# Main.net
KiCad netlist of a schematic drawn in Altium Designer
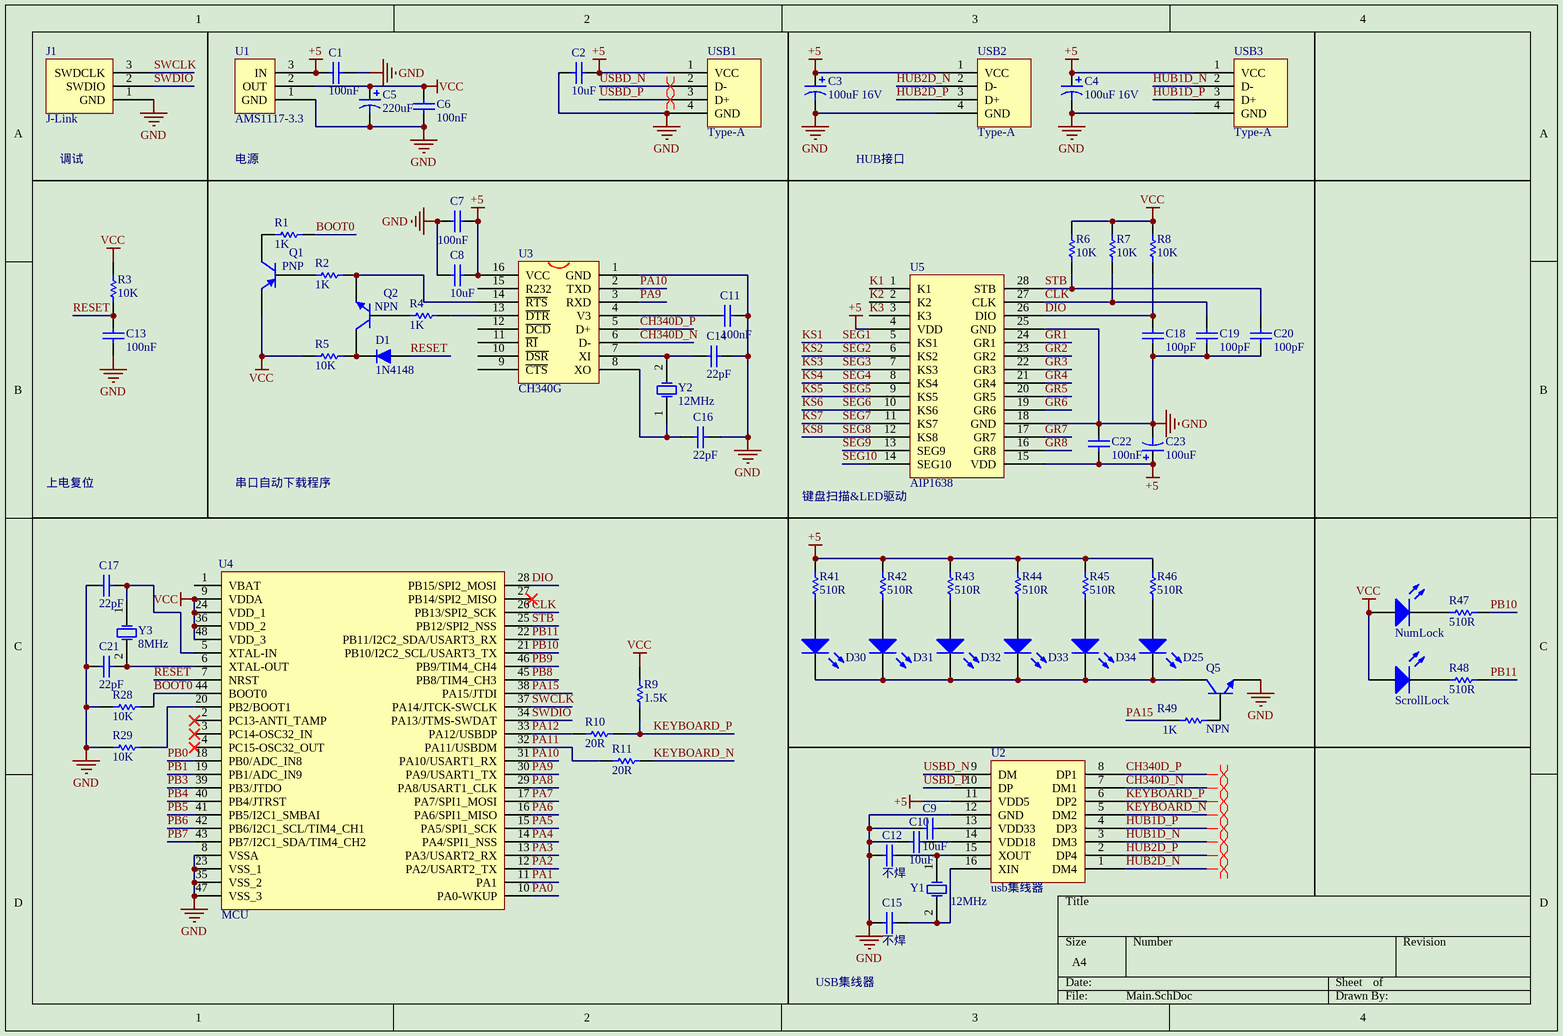
[diagram p0: Main.SchDoc]

(export (version "E")
  (design (tool "Eeschema 10.0.6"))
  (components
    (comp (ref "C1")
      (value "100nF")
      (footprint "LC-1206_C")
      (description "Capacitor")
      (fields (field (name "PUBLISHER") "Altium Limited"))
      (libsource (lib "键盘") (part "Capacitor"))
    )
    (comp (ref "C2")
      (value "10uF")
      (footprint "LC-0603_C")
      (description "Capacitor")
      (fields (field (name "PUBLISHER") "Altium Limited"))
      (libsource (lib "键盘") (part "Capacitor"))
    )
    (comp (ref "C3")
      (value "100uF 16V")
      (footprint "贴片电解 6.3*5.4")
      (description "Polarized Capacitor (Axial)")
      (fields (field (name "PUBLISHER") "Altium Limited"))
      (libsource (lib "键盘") (part "Cap Pol"))
    )
    (comp (ref "C4")
      (value "100uF 16V")
      (footprint "贴片电解 6.3*5.4")
      (description "Polarized Capacitor (Axial)")
      (fields (field (name "PUBLISHER") "Altium Limited"))
      (libsource (lib "键盘") (part "Cap Pol"))
    )
    (comp (ref "C5")
      (value "220uF")
      (footprint "自用库:贴片电解 8*10.2")
      (description "Polarized Capacitor (Axial)")
      (fields (field (name "PUBLISHER") "Altium Limited"))
      (libsource (lib "键盘") (part "Cap Pol"))
    )
    (comp (ref "C6")
      (value "100nF")
      (footprint "LC-1206_C")
      (description "Capacitor")
      (fields (field (name "PUBLISHER") "Altium Limited"))
      (libsource (lib "键盘") (part "Capacitor"))
    )
    (comp (ref "C7")
      (value "100nF")
      (footprint "LC-1206_C")
      (description "Capacitor")
      (fields (field (name "PUBLISHER") "Altium Limited"))
      (libsource (lib "键盘") (part "Capacitor"))
    )
    (comp (ref "C8")
      (value "10uF")
      (footprint "LC-0603_C")
      (description "Capacitor")
      (fields (field (name "PUBLISHER") "Altium Limited"))
      (libsource (lib "键盘") (part "Capacitor"))
    )
    (comp (ref "C9")
      (value "10uF")
      (footprint "LC-0603_C")
      (description "Capacitor")
      (fields (field (name "PUBLISHER") "Altium Limited"))
      (libsource (lib "键盘") (part "Capacitor"))
    )
    (comp (ref "C10")
      (value "10uF")
      (footprint "LC-0603_C")
      (description "Capacitor")
      (fields (field (name "PUBLISHER") "Altium Limited"))
      (libsource (lib "键盘") (part "Capacitor"))
    )
    (comp (ref "C11")
      (value "100nF")
      (footprint "LC-1206_C")
      (description "Capacitor")
      (fields (field (name "PUBLISHER") "Altium Limited"))
      (libsource (lib "键盘") (part "Capacitor"))
    )
    (comp (ref "C12")
      (value "不焊")
      (footprint "LC-0603_C")
      (description "Capacitor")
      (fields (field (name "PUBLISHER") "Altium Limited"))
      (libsource (lib "键盘") (part "Capacitor"))
    )
    (comp (ref "C13")
      (value "100nF")
      (footprint "LC-1206_C")
      (description "Capacitor")
      (fields (field (name "PUBLISHER") "Altium Limited"))
      (libsource (lib "Keyboard") (part "Capacitor"))
    )
    (comp (ref "C14")
      (value "22pF")
      (footprint "LC-1206_C")
      (description "Capacitor")
      (fields (field (name "PUBLISHER") "Altium Limited"))
      (libsource (lib "键盘") (part "Capacitor"))
    )
    (comp (ref "C15")
      (value "不焊")
      (footprint "LC-0603_C")
      (description "Capacitor")
      (fields (field (name "PUBLISHER") "Altium Limited"))
      (libsource (lib "键盘") (part "Capacitor"))
    )
    (comp (ref "C16")
      (value "22pF")
      (footprint "LC-1206_C")
      (description "Capacitor")
      (fields (field (name "PUBLISHER") "Altium Limited"))
      (libsource (lib "键盘") (part "Capacitor"))
    )
    (comp (ref "C17")
      (value "22pF")
      (footprint "LC-1206_C")
      (description "Capacitor")
      (fields (field (name "PUBLISHER") "Altium Limited"))
      (libsource (lib "键盘") (part "Capacitor"))
    )
    (comp (ref "C18")
      (value "100pF")
      (footprint "LC-0603_C")
      (description "Capacitor")
      (fields (field (name "PUBLISHER") "Altium Limited"))
      (libsource (lib "键盘") (part "Capacitor"))
    )
    (comp (ref "C19")
      (value "100pF")
      (footprint "LC-0603_C")
      (description "Capacitor")
      (fields (field (name "PUBLISHER") "Altium Limited"))
      (libsource (lib "键盘") (part "Capacitor"))
    )
    (comp (ref "C20")
      (value "100pF")
      (footprint "LC-0603_C")
      (description "Capacitor")
      (fields (field (name "PUBLISHER") "Altium Limited"))
      (libsource (lib "键盘") (part "Capacitor"))
    )
    (comp (ref "C21")
      (value "22pF")
      (footprint "LC-1206_C")
      (description "Capacitor")
      (fields (field (name "PUBLISHER") "Altium Limited"))
      (libsource (lib "键盘") (part "Capacitor"))
    )
    (comp (ref "C22")
      (value "100nF")
      (footprint "LC-1206_C")
      (description "Capacitor")
      (fields (field (name "PUBLISHER") "Altium Limited"))
      (libsource (lib "键盘") (part "Capacitor"))
    )
    (comp (ref "C23")
      (value "100uF")
      (footprint "贴片电解 6.3*5.4")
      (description "Polarized Capacitor (Axial)")
      (fields (field (name "PUBLISHER") "Altium Limited"))
      (libsource (lib "键盘") (part "Cap Pol"))
    )
    (comp (ref "D1") (value "1N4148") (footprint "LC-DO-35") (libsource (lib "自用库") (part "DO-214AC 肖特基")))
    (comp (ref "D25")
      (value "LED")
      (footprint "LC-0603_LED_S3")
      (description "Typical INFRARED GaAs LED")
      (fields (field (name "PUBLISHER") "Altium Limited"))
      (libsource (lib "键盘") (part "LED"))
    )
    (comp (ref "D30")
      (value "LED")
      (footprint "LC-0603_LED_S3")
      (description "Typical INFRARED GaAs LED")
      (fields (field (name "PUBLISHER") "Altium Limited"))
      (libsource (lib "键盘") (part "LED"))
    )
    (comp (ref "D31")
      (value "LED")
      (footprint "LC-0603_LED_S3")
      (description "Typical INFRARED GaAs LED")
      (fields (field (name "PUBLISHER") "Altium Limited"))
      (libsource (lib "键盘") (part "LED"))
    )
    (comp (ref "D32")
      (value "LED")
      (footprint "LC-0603_LED_S3")
      (description "Typical INFRARED GaAs LED")
      (fields (field (name "PUBLISHER") "Altium Limited"))
      (libsource (lib "键盘") (part "LED"))
    )
    (comp (ref "D33")
      (value "LED")
      (footprint "LC-0603_LED_S3")
      (description "Typical INFRARED GaAs LED")
      (fields (field (name "PUBLISHER") "Altium Limited"))
      (libsource (lib "键盘") (part "LED"))
    )
    (comp (ref "D34")
      (value "LED")
      (footprint "LC-0603_LED_S3")
      (description "Typical INFRARED GaAs LED")
      (fields (field (name "PUBLISHER") "Altium Limited"))
      (libsource (lib "键盘") (part "LED"))
    )
    (comp (ref "J1") (value "J-Link") (footprint "IDE3") (libsource (lib "键盘") (part "J-Link")))
    (comp (ref "NumLock")
      (value "LED")
      (footprint "LC-0603_LED_S3")
      (description "Typical INFRARED GaAs LED")
      (fields (field (name "PUBLISHER") "Altium Limited"))
      (libsource (lib "键盘") (part "LED"))
    )
    (comp (ref "Q1")
      (value "PNP")
      (footprint "LC-SOT-23(SOT-23-3)")
      (description "PNP Bipolar Transistor")
      (fields (field (name "PUBLISHER") "Altium Limited"))
      (libsource (lib "键盘") (part "PNP"))
    )
    (comp (ref "Q2")
      (value "NPN")
      (footprint "LC-SOT-23(SOT-23-3)")
      (description "NPN Bipolar Transistor")
      (fields (field (name "PUBLISHER") "Altium Limited"))
      (libsource (lib "键盘") (part "NPN"))
    )
    (comp (ref "Q5")
      (value "NPN")
      (footprint "LC-SOT-23(SOT-23-3)")
      (description "NPN Bipolar Transistor")
      (fields (field (name "PUBLISHER") "Altium Limited"))
      (libsource (lib "键盘") (part "NPN"))
    )
    (comp (ref "R1")
      (value "1K")
      (footprint "LC-0603_R")
      (description "Resistor")
      (fields (field (name "PUBLISHER") "Altium Limited"))
      (libsource (lib "键盘") (part "Resistor"))
    )
    (comp (ref "R2")
      (value "1K")
      (footprint "LC-0603_R")
      (description "Resistor")
      (fields (field (name "PUBLISHER") "Altium Limited"))
      (libsource (lib "键盘") (part "Resistor"))
    )
    (comp (ref "R3")
      (value "10K")
      (footprint "LC-1206_R")
      (description "Resistor")
      (fields (field (name "PUBLISHER") "Altium Limited"))
      (libsource (lib "Keyboard") (part "Resistor"))
    )
    (comp (ref "R4")
      (value "1K")
      (footprint "LC-0603_R")
      (description "Resistor")
      (fields (field (name "PUBLISHER") "Altium Limited"))
      (libsource (lib "键盘") (part "Resistor"))
    )
    (comp (ref "R5")
      (value "10K")
      (footprint "LC-1206_R")
      (description "Resistor")
      (fields (field (name "PUBLISHER") "Altium Limited"))
      (libsource (lib "键盘") (part "Resistor"))
    )
    (comp (ref "R6")
      (value "10K")
      (footprint "LC-1206_R")
      (description "Resistor")
      (fields (field (name "PUBLISHER") "Altium Limited"))
      (libsource (lib "键盘") (part "Resistor"))
    )
    (comp (ref "R7")
      (value "10K")
      (footprint "LC-1206_R")
      (description "Resistor")
      (fields (field (name "PUBLISHER") "Altium Limited"))
      (libsource (lib "键盘") (part "Resistor"))
    )
    (comp (ref "R8")
      (value "10K")
      (footprint "LC-1206_R")
      (description "Resistor")
      (fields (field (name "PUBLISHER") "Altium Limited"))
      (libsource (lib "键盘") (part "Resistor"))
    )
    (comp (ref "R9")
      (value "1.5K")
      (footprint "LC-1206_R")
      (description "Resistor")
      (fields (field (name "PUBLISHER") "Altium Limited"))
      (libsource (lib "键盘") (part "Resistor"))
    )
    (comp (ref "R10")
      (value "20R")
      (footprint "LC-0603_R")
      (description "Resistor")
      (fields (field (name "PUBLISHER") "Altium Limited"))
      (libsource (lib "键盘") (part "Resistor"))
    )
    (comp (ref "R11")
      (value "20R")
      (footprint "LC-0603_R")
      (description "Resistor")
      (fields (field (name "PUBLISHER") "Altium Limited"))
      (libsource (lib "键盘") (part "Resistor"))
    )
    (comp (ref "R28")
      (value "10K")
      (footprint "LC-1206_R")
      (description "Resistor")
      (fields (field (name "PUBLISHER") "Altium Limited"))
      (libsource (lib "键盘") (part "Resistor"))
    )
    (comp (ref "R29")
      (value "10K")
      (footprint "LC-1206_R")
      (description "Resistor")
      (fields (field (name "PUBLISHER") "Altium Limited"))
      (libsource (lib "键盘") (part "Resistor"))
    )
    (comp (ref "R41")
      (value "510R")
      (footprint "LC-0603_R")
      (description "Resistor")
      (fields (field (name "PUBLISHER") "Altium Limited"))
      (libsource (lib "键盘") (part "Resistor"))
    )
    (comp (ref "R42")
      (value "510R")
      (footprint "LC-0603_R")
      (description "Resistor")
      (fields (field (name "PUBLISHER") "Altium Limited"))
      (libsource (lib "键盘") (part "Resistor"))
    )
    (comp (ref "R43")
      (value "510R")
      (footprint "LC-0603_R")
      (description "Resistor")
      (fields (field (name "PUBLISHER") "Altium Limited"))
      (libsource (lib "键盘") (part "Resistor"))
    )
    (comp (ref "R44")
      (value "510R")
      (footprint "LC-0603_R")
      (description "Resistor")
      (fields (field (name "PUBLISHER") "Altium Limited"))
      (libsource (lib "键盘") (part "Resistor"))
    )
    (comp (ref "R45")
      (value "510R")
      (footprint "LC-0603_R")
      (description "Resistor")
      (fields (field (name "PUBLISHER") "Altium Limited"))
      (libsource (lib "键盘") (part "Resistor"))
    )
    (comp (ref "R46")
      (value "510R")
      (footprint "LC-0603_R")
      (description "Resistor")
      (fields (field (name "PUBLISHER") "Altium Limited"))
      (libsource (lib "键盘") (part "Resistor"))
    )
    (comp (ref "R47")
      (value "510R")
      (footprint "LC-0603_R")
      (description "Resistor")
      (fields (field (name "PUBLISHER") "Altium Limited"))
      (libsource (lib "键盘") (part "Resistor"))
    )
    (comp (ref "R48")
      (value "510R")
      (footprint "LC-0603_R")
      (description "Resistor")
      (fields (field (name "PUBLISHER") "Altium Limited"))
      (libsource (lib "键盘") (part "Resistor"))
    )
    (comp (ref "R49")
      (value "1K")
      (footprint "LC-0603_R")
      (description "Resistor")
      (fields (field (name "PUBLISHER") "Altium Limited"))
      (libsource (lib "键盘") (part "Resistor"))
    )
    (comp (ref "ScrollLock")
      (value "LED")
      (footprint "LC-0603_LED_S3")
      (description "Typical INFRARED GaAs LED")
      (fields (field (name "PUBLISHER") "Altium Limited"))
      (libsource (lib "键盘") (part "LED"))
    )
    (comp (ref "U1") (value "AMS1117-3.3") (footprint "LC-SOT-223") (libsource (lib "键盘") (part "AMS1117")))
    (comp (ref "U2") (value "usb集线器") (footprint "LC-SOP-16_150mil") (libsource (lib "键盘") (part "SL2.1A")))
    (comp (ref "U3") (value "CH340G") (footprint "LC-SOP-16_150mil") (libsource (lib "键盘") (part "CH340")))
    (comp (ref "U4") (value "MCU") (footprint "lqfp48") (libsource (lib "键盘") (part "STM32F103C8T6")))
    (comp (ref "U5") (value "AIP1638") (footprint "LC-SOP-28_300mil") (libsource (lib "键盘") (part "AIP1638")))
    (comp (ref "USB1") (value "Type-A") (footprint "USB") (libsource (lib "键盘") (part "USB-A")))
    (comp (ref "USB2") (value "Type-A") (footprint "USB A型") (libsource (lib "键盘") (part "USB-A")))
    (comp (ref "USB3") (value "Type-A") (footprint "USB A型") (libsource (lib "键盘") (part "USB-A")))
    (comp (ref "Y1")
      (value "12MHz")
      (footprint "LC-HC-49S")
      (description "Crystal Oscillator")
      (fields (field (name "PUBLISHER") "Altium Limited"))
      (libsource (lib "键盘") (part "XTAL"))
    )
    (comp (ref "Y2")
      (value "12MHz")
      (footprint "LC-HC-49S")
      (description "Crystal Oscillator")
      (fields (field (name "PUBLISHER") "Altium Limited"))
      (libsource (lib "键盘") (part "XTAL"))
    )
    (comp (ref "Y3")
      (value "8MHz")
      (footprint "LC-HC-49S")
      (description "Crystal Oscillator")
      (fields (field (name "PUBLISHER") "Altium Limited"))
      (libsource (lib "键盘") (part "XTAL"))
    )
  )
  (nets
    (net (code "1") (name "+5") (class "Default")
      (node (ref "C1") (pin "2") (pinfunction "2_2") (pintype "passive"))
      (node (ref "C2") (pin "1") (pinfunction "1_1") (pintype "passive"))
      (node (ref "C22") (pin "1") (pinfunction "1_1") (pintype "passive"))
      (node (ref "C23") (pin "1") (pinfunction "1_1") (pintype "passive"))
      (node (ref "C3") (pin "1") (pinfunction "1_1") (pintype "passive"))
      (node (ref "C4") (pin "1") (pinfunction "1_1") (pintype "passive"))
      (node (ref "C7") (pin "2") (pinfunction "2_2") (pintype "passive"))
      (node (ref "C8") (pin "1") (pinfunction "1_1") (pintype "passive"))
      (node (ref "R41") (pin "2") (pinfunction "2_2") (pintype "passive"))
      (node (ref "R42") (pin "2") (pinfunction "2_2") (pintype "passive"))
      (node (ref "R43") (pin "2") (pinfunction "2_2") (pintype "passive"))
      (node (ref "R44") (pin "2") (pinfunction "2_2") (pintype "passive"))
      (node (ref "R45") (pin "2") (pinfunction "2_2") (pintype "passive"))
      (node (ref "R46") (pin "2") (pinfunction "2_2") (pintype "passive"))
      (node (ref "U1") (pin "3") (pinfunction "IN_3") (pintype "passive"))
      (node (ref "U2") (pin "11") (pinfunction "VDD5_11") (pintype "passive"))
      (node (ref "U3") (pin "16") (pinfunction "VCC_16") (pintype "passive"))
      (node (ref "U5") (pin "15") (pinfunction "VDD_15") (pintype "passive"))
      (node (ref "U5") (pin "4") (pinfunction "VDD_4") (pintype "passive"))
      (node (ref "USB1") (pin "1") (pinfunction "VCC_1") (pintype "passive"))
      (node (ref "USB2") (pin "1") (pinfunction "VCC_1") (pintype "passive"))
      (node (ref "USB3") (pin "1") (pinfunction "VCC_1") (pintype "passive"))
    )
    (net (code "2") (name "/BOOT0") (class "Default")
      (node (ref "R1") (pin "2") (pinfunction "2_2") (pintype "passive"))
      (node (ref "R28") (pin "2") (pinfunction "2_2") (pintype "passive"))
      (node (ref "U4") (pin "44") (pinfunction "BOOT0_44") (pintype "passive"))
    )
    (net (code "3") (name "/CH340D_N") (class "Default")
      (node (ref "U2") (pin "7") (pinfunction "DM1_7") (pintype "passive"))
      (node (ref "U3") (pin "6") (pinfunction "D-_6") (pintype "passive"))
    )
    (net (code "4") (name "/CH340D_P") (class "Default")
      (node (ref "U2") (pin "8") (pinfunction "DP1_8") (pintype "passive"))
      (node (ref "U3") (pin "5") (pinfunction "D+_5") (pintype "passive"))
    )
    (net (code "5") (name "/CLK") (class "Default")
      (node (ref "C19") (pin "2") (pinfunction "2_2") (pintype "passive"))
      (node (ref "R7") (pin "1") (pinfunction "1_1") (pintype "passive"))
      (node (ref "U4") (pin "26") (pinfunction "PB13/SPI2_SCK_26") (pintype "passive"))
      (node (ref "U5") (pin "27") (pinfunction "CLK_27") (pintype "passive"))
    )
    (net (code "6") (name "/DIO") (class "Default")
      (node (ref "C18") (pin "2") (pinfunction "2_2") (pintype "passive"))
      (node (ref "R8") (pin "1") (pinfunction "1_1") (pintype "passive"))
      (node (ref "U4") (pin "28") (pinfunction "PB15/SPI2_MOSI_28") (pintype "passive"))
      (node (ref "U5") (pin "26") (pinfunction "DIO_26") (pintype "passive"))
    )
    (net (code "7") (name "/GR1") (class "Default")
      (node (ref "U5") (pin "24") (pinfunction "GR1_24") (pintype "passive"))
    )
    (net (code "8") (name "/GR2") (class "Default")
      (node (ref "U5") (pin "23") (pinfunction "GR2_23") (pintype "passive"))
    )
    (net (code "9") (name "/GR3") (class "Default")
      (node (ref "U5") (pin "22") (pinfunction "GR3_22") (pintype "passive"))
    )
    (net (code "10") (name "/GR4") (class "Default")
      (node (ref "U5") (pin "21") (pinfunction "GR4_21") (pintype "passive"))
    )
    (net (code "11") (name "/GR5") (class "Default")
      (node (ref "U5") (pin "20") (pinfunction "GR5_20") (pintype "passive"))
    )
    (net (code "12") (name "/GR6") (class "Default")
      (node (ref "U5") (pin "19") (pinfunction "GR6_19") (pintype "passive"))
    )
    (net (code "13") (name "/GR7") (class "Default")
      (node (ref "U5") (pin "17") (pinfunction "GR7_17") (pintype "passive"))
    )
    (net (code "14") (name "/GR8") (class "Default")
      (node (ref "U5") (pin "16") (pinfunction "GR8_16") (pintype "passive"))
    )
    (net (code "15") (name "/HUB1D_N") (class "Default")
      (node (ref "U2") (pin "3") (pinfunction "DM3_3") (pintype "passive"))
      (node (ref "USB3") (pin "2") (pinfunction "D-_2") (pintype "passive"))
    )
    (net (code "16") (name "/HUB1D_P") (class "Default")
      (node (ref "U2") (pin "4") (pinfunction "DP3_4") (pintype "passive"))
      (node (ref "USB3") (pin "3") (pinfunction "D+_3") (pintype "passive"))
    )
    (net (code "17") (name "/HUB2D_N") (class "Default")
      (node (ref "U2") (pin "1") (pinfunction "DM4_1") (pintype "passive"))
      (node (ref "USB2") (pin "2") (pinfunction "D-_2") (pintype "passive"))
    )
    (net (code "18") (name "/HUB2D_P") (class "Default")
      (node (ref "U2") (pin "2") (pinfunction "DP4_2") (pintype "passive"))
      (node (ref "USB2") (pin "3") (pinfunction "D+_3") (pintype "passive"))
    )
    (net (code "19") (name "/K1") (class "Default")
      (node (ref "U5") (pin "1") (pinfunction "K1_1") (pintype "passive"))
    )
    (net (code "20") (name "/K2") (class "Default")
      (node (ref "U5") (pin "2") (pinfunction "K2_2") (pintype "passive"))
    )
    (net (code "21") (name "/K3") (class "Default")
      (node (ref "U5") (pin "3") (pinfunction "K3_3") (pintype "passive"))
    )
    (net (code "22") (name "/KEYBOARD_N") (class "Default")
      (node (ref "R11") (pin "2") (pinfunction "2_2") (pintype "passive"))
      (node (ref "U2") (pin "5") (pinfunction "DM2_5") (pintype "passive"))
    )
    (net (code "23") (name "/KEYBOARD_P") (class "Default")
      (node (ref "R10") (pin "2") (pinfunction "2_2") (pintype "passive"))
      (node (ref "R9") (pin "1") (pinfunction "1_1") (pintype "passive"))
      (node (ref "U2") (pin "6") (pinfunction "DP2_6") (pintype "passive"))
    )
    (net (code "24") (name "/KS1") (class "Default")
      (node (ref "U5") (pin "5") (pinfunction "KS1_5") (pintype "passive"))
    )
    (net (code "25") (name "/KS2") (class "Default")
      (node (ref "U5") (pin "6") (pinfunction "KS2_6") (pintype "passive"))
    )
    (net (code "26") (name "/KS3") (class "Default")
      (node (ref "U5") (pin "7") (pinfunction "KS3_7") (pintype "passive"))
    )
    (net (code "27") (name "/KS4") (class "Default")
      (node (ref "U5") (pin "8") (pinfunction "KS4_8") (pintype "passive"))
    )
    (net (code "28") (name "/KS5") (class "Default")
      (node (ref "U5") (pin "9") (pinfunction "KS5_9") (pintype "passive"))
    )
    (net (code "29") (name "/KS6") (class "Default")
      (node (ref "U5") (pin "10") (pinfunction "KS6_10") (pintype "passive"))
    )
    (net (code "30") (name "/KS7") (class "Default")
      (node (ref "U5") (pin "11") (pinfunction "KS7_11") (pintype "passive"))
    )
    (net (code "31") (name "/KS8") (class "Default")
      (node (ref "U5") (pin "12") (pinfunction "KS8_12") (pintype "passive"))
    )
    (net (code "32") (name "/PA0") (class "Default")
      (node (ref "U4") (pin "10") (pinfunction "PA0-WKUP_10") (pintype "passive"))
    )
    (net (code "33") (name "/PA1") (class "Default")
      (node (ref "U4") (pin "11") (pinfunction "PA1_11") (pintype "passive"))
    )
    (net (code "34") (name "/PA2") (class "Default")
      (node (ref "U4") (pin "12") (pinfunction "PA2/USART2_TX_12") (pintype "passive"))
    )
    (net (code "35") (name "/PA3") (class "Default")
      (node (ref "U4") (pin "13") (pinfunction "PA3/USART2_RX_13") (pintype "passive"))
    )
    (net (code "36") (name "/PA4") (class "Default")
      (node (ref "U4") (pin "14") (pinfunction "PA4/SPI1_NSS_14") (pintype "passive"))
    )
    (net (code "37") (name "/PA5") (class "Default")
      (node (ref "U4") (pin "15") (pinfunction "PA5/SPI1_SCK_15") (pintype "passive"))
    )
    (net (code "38") (name "/PA6") (class "Default")
      (node (ref "U4") (pin "16") (pinfunction "PA6/SPI1_MISO_16") (pintype "passive"))
    )
    (net (code "39") (name "/PA7") (class "Default")
      (node (ref "U4") (pin "17") (pinfunction "PA7/SPI1_MOSI_17") (pintype "passive"))
    )
    (net (code "40") (name "/PA8") (class "Default")
      (node (ref "U4") (pin "29") (pinfunction "PA8/USART1_CLK_29") (pintype "passive"))
    )
    (net (code "41") (name "/PA9") (class "Default")
      (node (ref "U3") (pin "3") (pinfunction "RXD_3") (pintype "passive"))
      (node (ref "U4") (pin "30") (pinfunction "PA9/USART1_TX_30") (pintype "passive"))
    )
    (net (code "42") (name "/PA10") (class "Default")
      (node (ref "U3") (pin "2") (pinfunction "TXD_2") (pintype "passive"))
      (node (ref "U4") (pin "31") (pinfunction "PA10/USART1_RX_31") (pintype "passive"))
    )
    (net (code "43") (name "/PA11") (class "Default")
      (node (ref "R11") (pin "1") (pinfunction "1_1") (pintype "passive"))
      (node (ref "U4") (pin "32") (pinfunction "PA11/USBDM_32") (pintype "passive"))
    )
    (net (code "44") (name "/PA12") (class "Default")
      (node (ref "R10") (pin "1") (pinfunction "1_1") (pintype "passive"))
      (node (ref "U4") (pin "33") (pinfunction "PA12/USBDP_33") (pintype "passive"))
    )
    (net (code "45") (name "/PA15") (class "Default")
      (node (ref "R49") (pin "1") (pinfunction "1_1") (pintype "passive"))
      (node (ref "U4") (pin "38") (pinfunction "PA15/JTDI_38") (pintype "passive"))
    )
    (net (code "46") (name "/PB0") (class "Default")
      (node (ref "U4") (pin "18") (pinfunction "PB0/ADC_IN8_18") (pintype "passive"))
    )
    (net (code "47") (name "/PB1") (class "Default")
      (node (ref "U4") (pin "19") (pinfunction "PB1/ADC_IN9_19") (pintype "passive"))
    )
    (net (code "48") (name "/PB3") (class "Default")
      (node (ref "U4") (pin "39") (pinfunction "PB3/JTDO_39") (pintype "passive"))
    )
    (net (code "49") (name "/PB4") (class "Default")
      (node (ref "U4") (pin "40") (pinfunction "PB4/JTRST_40") (pintype "passive"))
    )
    (net (code "50") (name "/PB5") (class "Default")
      (node (ref "U4") (pin "41") (pinfunction "PB5/I2C1_SMBAI_41") (pintype "passive"))
    )
    (net (code "51") (name "/PB6") (class "Default")
      (node (ref "U4") (pin "42") (pinfunction "PB6/I2C1_SCL/TIM4_CH1_42") (pintype "passive"))
    )
    (net (code "52") (name "/PB7") (class "Default")
      (node (ref "U4") (pin "43") (pinfunction "PB7/I2C1_SDA/TIM4_CH2_43") (pintype "passive"))
    )
    (net (code "53") (name "/PB8") (class "Default")
      (node (ref "U4") (pin "45") (pinfunction "PB8/TIM4_CH3_45") (pintype "passive"))
    )
    (net (code "54") (name "/PB9") (class "Default")
      (node (ref "U4") (pin "46") (pinfunction "PB9/TIM4_CH4_46") (pintype "passive"))
    )
    (net (code "55") (name "/PB10") (class "Default")
      (node (ref "R47") (pin "2") (pinfunction "2_2") (pintype "passive"))
      (node (ref "U4") (pin "21") (pinfunction "PB10/I2C2_SCL/USART3_TX_21") (pintype "passive"))
    )
    (net (code "56") (name "/PB11") (class "Default")
      (node (ref "R48") (pin "2") (pinfunction "2_2") (pintype "passive"))
      (node (ref "U4") (pin "22") (pinfunction "PB11/I2C2_SDA/USART3_RX_22") (pintype "passive"))
    )
    (net (code "57") (name "/RESET") (class "Default")
      (node (ref "C13") (pin "2") (pinfunction "2_2") (pintype "passive"))
      (node (ref "D1") (pin "1") (pinfunction "A_1") (pintype "passive"))
      (node (ref "R3") (pin "1") (pinfunction "1_1") (pintype "passive"))
      (node (ref "U4") (pin "7") (pinfunction "NRST_7") (pintype "passive"))
    )
    (net (code "58") (name "/SEG9") (class "Default")
      (node (ref "U5") (pin "13") (pinfunction "SEG9_13") (pintype "passive"))
    )
    (net (code "59") (name "/SEG10") (class "Default")
      (node (ref "U5") (pin "14") (pinfunction "SEG10_14") (pintype "passive"))
    )
    (net (code "60") (name "/STB") (class "Default")
      (node (ref "C20") (pin "2") (pinfunction "2_2") (pintype "passive"))
      (node (ref "R6") (pin "1") (pinfunction "1_1") (pintype "passive"))
      (node (ref "U4") (pin "25") (pinfunction "PB12/SPI2_NSS_25") (pintype "passive"))
      (node (ref "U5") (pin "28") (pinfunction "STB_28") (pintype "passive"))
    )
    (net (code "61") (name "/SWCLK") (class "Default")
      (node (ref "J1") (pin "3") (pinfunction "SWDCLK_3") (pintype "passive"))
      (node (ref "U4") (pin "37") (pinfunction "PA14/JTCK-SWCLK_37") (pintype "passive"))
    )
    (net (code "62") (name "/SWDIO") (class "Default")
      (node (ref "J1") (pin "2") (pinfunction "SWDIO_2") (pintype "passive"))
      (node (ref "U4") (pin "34") (pinfunction "PA13/JTMS-SWDAT_34") (pintype "passive"))
    )
    (net (code "63") (name "/USBD_N") (class "Default")
      (node (ref "U2") (pin "9") (pinfunction "DM_9") (pintype "passive"))
      (node (ref "USB1") (pin "2") (pinfunction "D-_2") (pintype "passive"))
    )
    (net (code "64") (name "/USBD_P") (class "Default")
      (node (ref "U2") (pin "10") (pinfunction "DP_10") (pintype "passive"))
      (node (ref "USB1") (pin "3") (pinfunction "D+_3") (pintype "passive"))
    )
    (net (code "65") (name "GND") (class "Default")
      (node (ref "C1") (pin "1") (pinfunction "1_1") (pintype "passive"))
      (node (ref "C10") (pin "2") (pinfunction "2_2") (pintype "passive"))
      (node (ref "C11") (pin "2") (pinfunction "2_2") (pintype "passive"))
      (node (ref "C12") (pin "2") (pinfunction "2_2") (pintype "passive"))
      (node (ref "C13") (pin "1") (pinfunction "1_1") (pintype "passive"))
      (node (ref "C14") (pin "2") (pinfunction "2_2") (pintype "passive"))
      (node (ref "C15") (pin "2") (pinfunction "2_2") (pintype "passive"))
      (node (ref "C16") (pin "2") (pinfunction "2_2") (pintype "passive"))
      (node (ref "C17") (pin "1") (pinfunction "1_1") (pintype "passive"))
      (node (ref "C18") (pin "1") (pinfunction "1_1") (pintype "passive"))
      (node (ref "C19") (pin "1") (pinfunction "1_1") (pintype "passive"))
      (node (ref "C2") (pin "2") (pinfunction "2_2") (pintype "passive"))
      (node (ref "C20") (pin "1") (pinfunction "1_1") (pintype "passive"))
      (node (ref "C21") (pin "1") (pinfunction "1_1") (pintype "passive"))
      (node (ref "C22") (pin "2") (pinfunction "2_2") (pintype "passive"))
      (node (ref "C23") (pin "2") (pinfunction "2_2") (pintype "passive"))
      (node (ref "C3") (pin "2") (pinfunction "2_2") (pintype "passive"))
      (node (ref "C4") (pin "2") (pinfunction "2_2") (pintype "passive"))
      (node (ref "C5") (pin "2") (pinfunction "2_2") (pintype "passive"))
      (node (ref "C6") (pin "2") (pinfunction "2_2") (pintype "passive"))
      (node (ref "C7") (pin "1") (pinfunction "1_1") (pintype "passive"))
      (node (ref "C8") (pin "2") (pinfunction "2_2") (pintype "passive"))
      (node (ref "C9") (pin "2") (pinfunction "2_2") (pintype "passive"))
      (node (ref "J1") (pin "1") (pinfunction "GND_1") (pintype "passive"))
      (node (ref "Q5") (pin "3") (pinfunction "E_3") (pintype "passive"))
      (node (ref "R28") (pin "1") (pinfunction "1_1") (pintype "passive"))
      (node (ref "R29") (pin "1") (pinfunction "1_1") (pintype "passive"))
      (node (ref "U1") (pin "1") (pinfunction "GND_1") (pintype "passive"))
      (node (ref "U2") (pin "12") (pinfunction "GND_12") (pintype "passive"))
      (node (ref "U3") (pin "1") (pinfunction "GND_1") (pintype "passive"))
      (node (ref "U4") (pin "23") (pinfunction "VSS_1_23") (pintype "passive"))
      (node (ref "U4") (pin "35") (pinfunction "VSS_2_35") (pintype "passive"))
      (node (ref "U4") (pin "47") (pinfunction "VSS_3_47") (pintype "passive"))
      (node (ref "U4") (pin "8") (pinfunction "VSSA_8") (pintype "passive"))
      (node (ref "U5") (pin "18") (pinfunction "GND_18") (pintype "passive"))
      (node (ref "U5") (pin "25") (pinfunction "GND_25") (pintype "passive"))
      (node (ref "USB1") (pin "4") (pinfunction "GND_4") (pintype "passive"))
      (node (ref "USB2") (pin "4") (pinfunction "GND_4") (pintype "passive"))
      (node (ref "USB3") (pin "4") (pinfunction "GND_4") (pintype "passive"))
    )
    (net (code "66") (name "Net-(D1-K)") (class "Default")
      (node (ref "D1") (pin "2") (pinfunction "K_2") (pintype "passive"))
      (node (ref "Q2") (pin "1") (pinfunction "C_1") (pintype "passive"))
      (node (ref "R5") (pin "2") (pinfunction "2_2") (pintype "passive"))
    )
    (net (code "67") (name "Net-(D25-1)") (class "Default")
      (node (ref "D25") (pin "A") (pinfunction "1_A") (pintype "passive"))
      (node (ref "R46") (pin "1") (pinfunction "1_1") (pintype "passive"))
    )
    (net (code "68") (name "Net-(D25-2)") (class "Default")
      (node (ref "D25") (pin "K") (pinfunction "2_K") (pintype "passive"))
      (node (ref "D30") (pin "K") (pinfunction "2_K") (pintype "passive"))
      (node (ref "D31") (pin "K") (pinfunction "2_K") (pintype "passive"))
      (node (ref "D32") (pin "K") (pinfunction "2_K") (pintype "passive"))
      (node (ref "D33") (pin "K") (pinfunction "2_K") (pintype "passive"))
      (node (ref "D34") (pin "K") (pinfunction "2_K") (pintype "passive"))
      (node (ref "Q5") (pin "1") (pinfunction "C_1") (pintype "passive"))
    )
    (net (code "69") (name "Net-(D30-1)") (class "Default")
      (node (ref "D30") (pin "A") (pinfunction "1_A") (pintype "passive"))
      (node (ref "R41") (pin "1") (pinfunction "1_1") (pintype "passive"))
    )
    (net (code "70") (name "Net-(D31-1)") (class "Default")
      (node (ref "D31") (pin "A") (pinfunction "1_A") (pintype "passive"))
      (node (ref "R42") (pin "1") (pinfunction "1_1") (pintype "passive"))
    )
    (net (code "71") (name "Net-(D32-1)") (class "Default")
      (node (ref "D32") (pin "A") (pinfunction "1_A") (pintype "passive"))
      (node (ref "R43") (pin "1") (pinfunction "1_1") (pintype "passive"))
    )
    (net (code "72") (name "Net-(D33-1)") (class "Default")
      (node (ref "D33") (pin "A") (pinfunction "1_A") (pintype "passive"))
      (node (ref "R44") (pin "1") (pinfunction "1_1") (pintype "passive"))
    )
    (net (code "73") (name "Net-(D34-1)") (class "Default")
      (node (ref "D34") (pin "A") (pinfunction "1_A") (pintype "passive"))
      (node (ref "R45") (pin "1") (pinfunction "1_1") (pintype "passive"))
    )
    (net (code "74") (name "Net-(NumLock-2)") (class "Default")
      (node (ref "NumLock") (pin "K") (pinfunction "2_K") (pintype "passive"))
      (node (ref "R47") (pin "1") (pinfunction "1_1") (pintype "passive"))
    )
    (net (code "75") (name "Net-(Q1-B)") (class "Default")
      (node (ref "Q1") (pin "2") (pinfunction "B_2") (pintype "passive"))
      (node (ref "R2") (pin "1") (pinfunction "1_1") (pintype "passive"))
    )
    (net (code "76") (name "Net-(Q1-C)") (class "Default")
      (node (ref "Q1") (pin "1") (pinfunction "C_1") (pintype "passive"))
      (node (ref "R1") (pin "1") (pinfunction "1_1") (pintype "passive"))
    )
    (net (code "77") (name "Net-(Q2-B)") (class "Default")
      (node (ref "Q2") (pin "2") (pinfunction "B_2") (pintype "passive"))
      (node (ref "R4") (pin "1") (pinfunction "1_1") (pintype "passive"))
    )
    (net (code "78") (name "Net-(Q2-E)") (class "Default")
      (node (ref "Q2") (pin "3") (pinfunction "E_3") (pintype "passive"))
      (node (ref "R2") (pin "2") (pinfunction "2_2") (pintype "passive"))
      (node (ref "U3") (pin "14") (pinfunction "~{RTS}_14") (pintype "passive"))
    )
    (net (code "79") (name "Net-(Q5-B)") (class "Default")
      (node (ref "Q5") (pin "2") (pinfunction "B_2") (pintype "passive"))
      (node (ref "R49") (pin "2") (pinfunction "2_2") (pintype "passive"))
    )
    (net (code "80") (name "Net-(ScrollLock-2)") (class "Default")
      (node (ref "R48") (pin "1") (pinfunction "1_1") (pintype "passive"))
      (node (ref "ScrollLock") (pin "K") (pinfunction "2_K") (pintype "passive"))
    )
    (net (code "81") (name "Net-(U2-VDD18)") (class "Default")
      (node (ref "C10") (pin "1") (pinfunction "1_1") (pintype "passive"))
      (node (ref "U2") (pin "14") (pinfunction "VDD18_14") (pintype "passive"))
    )
    (net (code "82") (name "Net-(U2-VDD33)") (class "Default")
      (node (ref "C9") (pin "1") (pinfunction "1_1") (pintype "passive"))
      (node (ref "U2") (pin "13") (pinfunction "VDD33_13") (pintype "passive"))
    )
    (net (code "83") (name "Net-(U2-XIN)") (class "Default")
      (node (ref "C15") (pin "1") (pinfunction "1_1") (pintype "passive"))
      (node (ref "U2") (pin "16") (pinfunction "XIN_16") (pintype "passive"))
      (node (ref "Y1") (pin "2") (pinfunction "OSC2_2") (pintype "passive"))
    )
    (net (code "84") (name "Net-(U2-XOUT)") (class "Default")
      (node (ref "C12") (pin "1") (pinfunction "1_1") (pintype "passive"))
      (node (ref "U2") (pin "15") (pinfunction "XOUT_15") (pintype "passive"))
      (node (ref "Y1") (pin "1") (pinfunction "OSC1_1") (pintype "passive"))
    )
    (net (code "85") (name "Net-(U3-V3)") (class "Default")
      (node (ref "C11") (pin "1") (pinfunction "1_1") (pintype "passive"))
      (node (ref "U3") (pin "4") (pinfunction "V3_4") (pintype "passive"))
    )
    (net (code "86") (name "Net-(U3-XI)") (class "Default")
      (node (ref "C14") (pin "1") (pinfunction "1_1") (pintype "passive"))
      (node (ref "U3") (pin "7") (pinfunction "XI_7") (pintype "passive"))
      (node (ref "Y2") (pin "2") (pinfunction "OSC2_2") (pintype "passive"))
    )
    (net (code "87") (name "Net-(U3-XO)") (class "Default")
      (node (ref "C16") (pin "1") (pinfunction "1_1") (pintype "passive"))
      (node (ref "U3") (pin "8") (pinfunction "XO_8") (pintype "passive"))
      (node (ref "Y2") (pin "1") (pinfunction "OSC1_1") (pintype "passive"))
    )
    (net (code "88") (name "Net-(U3-~{DTR})") (class "Default")
      (node (ref "R4") (pin "2") (pinfunction "2_2") (pintype "passive"))
      (node (ref "U3") (pin "13") (pinfunction "~{DTR}_13") (pintype "passive"))
    )
    (net (code "89") (name "Net-(U4-PB2{slash}BOOT1)") (class "Default")
      (node (ref "R29") (pin "2") (pinfunction "2_2") (pintype "passive"))
      (node (ref "U4") (pin "20") (pinfunction "PB2/BOOT1_20") (pintype "passive"))
    )
    (net (code "90") (name "Net-(U4-XTAL-IN)") (class "Default")
      (node (ref "C17") (pin "2") (pinfunction "2_2") (pintype "passive"))
      (node (ref "U4") (pin "5") (pinfunction "XTAL-IN_5") (pintype "passive"))
      (node (ref "Y3") (pin "1") (pinfunction "OSC1_1") (pintype "passive"))
    )
    (net (code "91") (name "Net-(U4-XTAL-OUT)") (class "Default")
      (node (ref "C21") (pin "2") (pinfunction "2_2") (pintype "passive"))
      (node (ref "U4") (pin "6") (pinfunction "XTAL-OUT_6") (pintype "passive"))
      (node (ref "Y3") (pin "2") (pinfunction "OSC2_2") (pintype "passive"))
    )
    (net (code "92") (name "VCC") (class "Default")
      (node (ref "C5") (pin "1") (pinfunction "1_1") (pintype "passive"))
      (node (ref "C6") (pin "1") (pinfunction "1_1") (pintype "passive"))
      (node (ref "NumLock") (pin "A") (pinfunction "1_A") (pintype "passive"))
      (node (ref "Q1") (pin "3") (pinfunction "E_3") (pintype "passive"))
      (node (ref "R3") (pin "2") (pinfunction "2_2") (pintype "passive"))
      (node (ref "R5") (pin "1") (pinfunction "1_1") (pintype "passive"))
      (node (ref "R6") (pin "2") (pinfunction "2_2") (pintype "passive"))
      (node (ref "R7") (pin "2") (pinfunction "2_2") (pintype "passive"))
      (node (ref "R8") (pin "2") (pinfunction "2_2") (pintype "passive"))
      (node (ref "R9") (pin "2") (pinfunction "2_2") (pintype "passive"))
      (node (ref "ScrollLock") (pin "A") (pinfunction "1_A") (pintype "passive"))
      (node (ref "U1") (pin "2") (pinfunction "OUT_2") (pintype "passive"))
      (node (ref "U4") (pin "24") (pinfunction "VDD_1_24") (pintype "passive"))
      (node (ref "U4") (pin "36") (pinfunction "VDD_2_36") (pintype "passive"))
      (node (ref "U4") (pin "48") (pinfunction "VDD_3_48") (pintype "passive"))
      (node (ref "U4") (pin "9") (pinfunction "VDDA_9") (pintype "passive"))
    )
    (net (code "93") (name "unconnected-(U3-R232-Pad15)") (class "Default")
      (node (ref "U3") (pin "15") (pinfunction "R232_15") (pintype "passive"))
    )
    (net (code "94") (name "unconnected-(U3-~{CTS}-Pad9)") (class "Default")
      (node (ref "U3") (pin "9") (pinfunction "~{CTS}_9") (pintype "passive"))
    )
    (net (code "95") (name "unconnected-(U3-~{DCD}-Pad12)") (class "Default")
      (node (ref "U3") (pin "12") (pinfunction "~{DCD}_12") (pintype "passive"))
    )
    (net (code "96") (name "unconnected-(U3-~{DSR}-Pad10)") (class "Default")
      (node (ref "U3") (pin "10") (pinfunction "~{DSR}_10") (pintype "passive"))
    )
    (net (code "97") (name "unconnected-(U3-~{RI}-Pad11)") (class "Default")
      (node (ref "U3") (pin "11") (pinfunction "~{RI}_11") (pintype "passive"))
    )
    (net (code "98") (name "unconnected-(U4-PB14{slash}SPI2_MISO-Pad27)") (class "Default")
      (node (ref "U4") (pin "27") (pinfunction "PB14/SPI2_MISO_27") (pintype "passive+no_connect"))
    )
    (net (code "99") (name "unconnected-(U4-PC13-ANTI_TAMP-Pad2)") (class "Default")
      (node (ref "U4") (pin "2") (pinfunction "PC13-ANTI_TAMP_2") (pintype "passive+no_connect"))
    )
    (net (code "100") (name "unconnected-(U4-PC14-OSC32_IN-Pad3)") (class "Default")
      (node (ref "U4") (pin "3") (pinfunction "PC14-OSC32_IN_3") (pintype "passive+no_connect"))
    )
    (net (code "101") (name "unconnected-(U4-PC15-OSC32_OUT-Pad4)") (class "Default")
      (node (ref "U4") (pin "4") (pinfunction "PC15-OSC32_OUT_4") (pintype "passive+no_connect"))
    )
    (net (code "102") (name "unconnected-(U4-VBAT-Pad1)") (class "Default")
      (node (ref "U4") (pin "1") (pinfunction "VBAT_1") (pintype "passive"))
    )
  )
)
